# ESP32_CONTROLLER_SHEET.net
KiCad netlist of a schematic drawn in Altium Designer
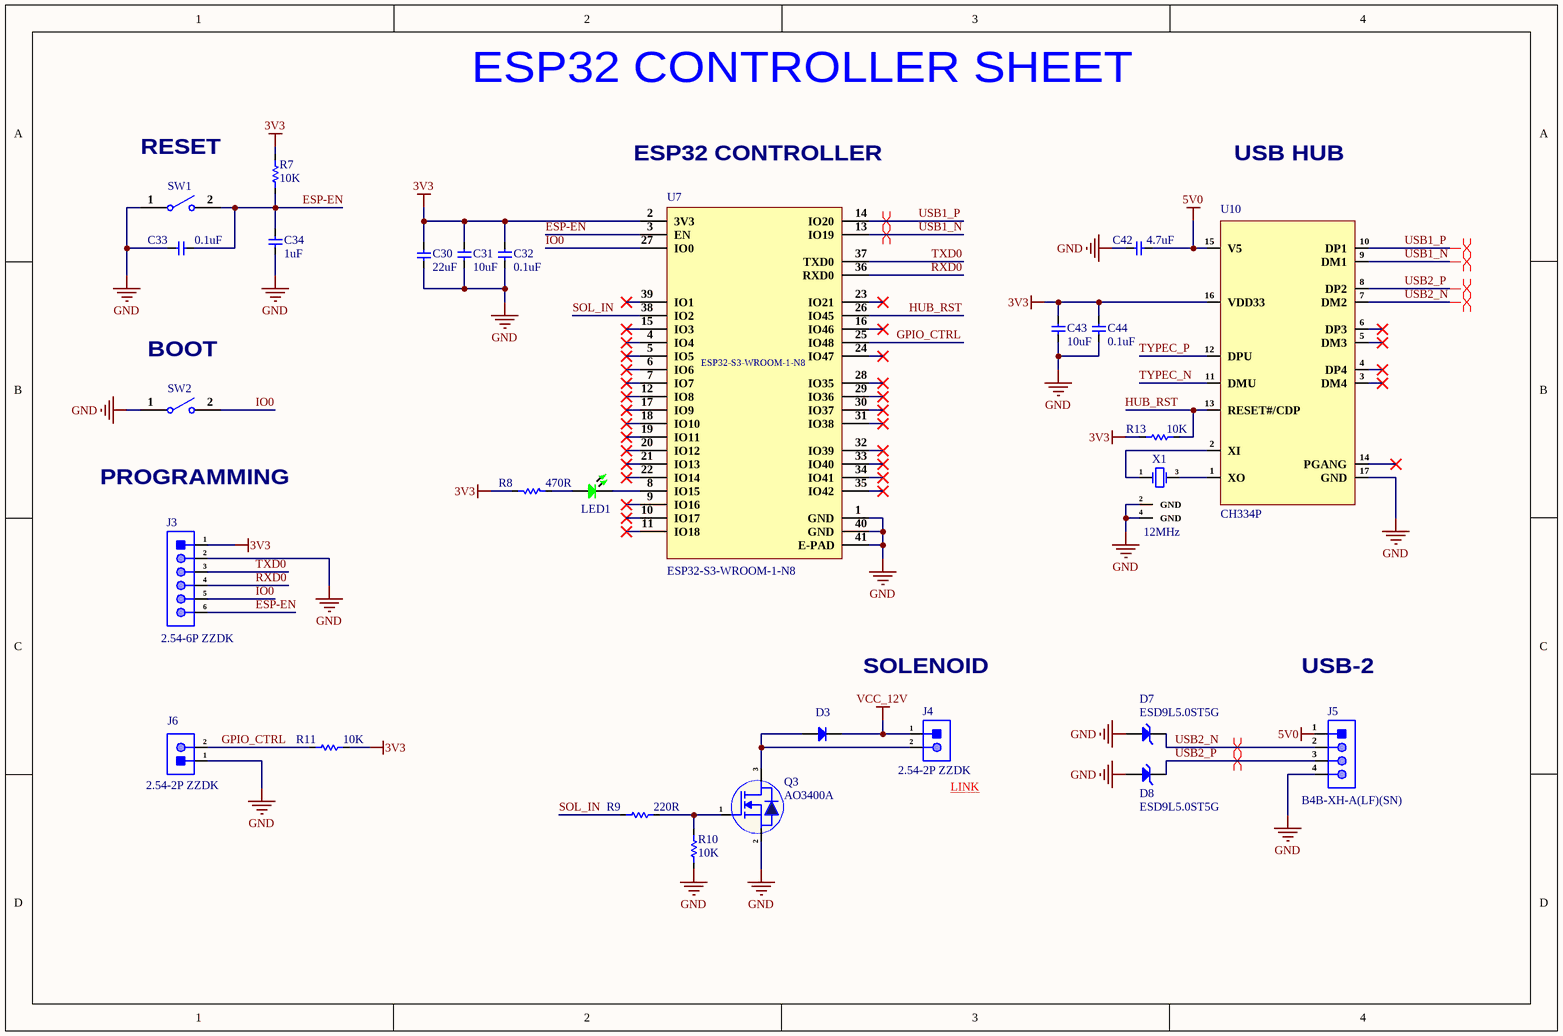
[diagram p0: ESP32_CONTROLLER_SHEET.SchDoc]

(export (version "E")
  (design (tool "Eeschema 10.0.6"))
  (components
    (comp (ref "C30")
      (value "22uF")
      (footprint "Cap-0603")
      (description "CAP CER 22UF 10V X5R 0603")
      (fields
        (field (name "MANUFACTURER") "Yageo")
        (field (name "MANUFACTURER PART NUMBER") "CC0603MRX5R6BB226")
      )
      (libsource (lib "eSpark Libraries") (part "CC0603MRX5R6BB226"))
    )
    (comp (ref "C31")
      (value "10uF")
      (footprint "Cap-0603")
      (description "CAP CER 10UF 16V X5R 0603")
      (fields
        (field (name "MANUFACTURER") "Yageo")
        (field (name "MANUFACTURER PART NUMBER") "CC0603KRX5R7BB106")
      )
      (libsource (lib "eSpark Libraries") (part "CC0603KRX5R7BB106"))
    )
    (comp (ref "C32")
      (value "0.1uF")
      (footprint "Cap-0402")
      (description "CAP CER 0.1UF 50V X7R 0402")
      (fields
        (field (name "MANUFACTURER") "Samsung")
        (field (name "MANUFACTURER PART NUMBER") "CL05B104KB54PNC")
      )
      (libsource (lib "eSpark Libraries") (part "CL05B104KB54PNC"))
    )
    (comp (ref "C33")
      (value "0.1uF")
      (footprint "Cap-0402")
      (description "CAP CER 0.1UF 50V X7R 0402")
      (fields
        (field (name "MANUFACTURER") "Samsung")
        (field (name "MANUFACTURER PART NUMBER") "CL05B104KB54PNC")
      )
      (libsource (lib "eSpark Libraries") (part "CL05B104KB54PNC"))
    )
    (comp (ref "C34")
      (value "1uF")
      (footprint "Cap-0402")
      (description "CAP CER 1UF 16V X5R 0402")
      (fields
        (field (name "MANUFACTURER") "Yageo")
        (field (name "MANUFACTURER PART NUMBER") "CC0402KRX5R7BB105")
      )
      (libsource (lib "eSpark Libraries") (part "CC0402KRX5R7BB105"))
    )
    (comp (ref "C42")
      (value "4.7uF")
      (footprint "Cap-0402")
      (description "CAP CER 4.7UF 16V X5R 0402")
      (fields
        (field (name "MANUFACTURER") "Samsung")
        (field (name "MANUFACTURER PART NUMBER") "CL05A475MO5NUNC")
      )
      (libsource (lib "eSpark Libraries") (part "CL05A475MO5NUNC"))
    )
    (comp (ref "C43")
      (value "10uF")
      (footprint "Cap-0603")
      (description "CAP CER 10UF 16V X5R 0603")
      (fields
        (field (name "MANUFACTURER") "Yageo")
        (field (name "MANUFACTURER PART NUMBER") "CC0603KRX5R7BB106")
      )
      (libsource (lib "eSpark Libraries") (part "CC0603KRX5R7BB106"))
    )
    (comp (ref "C44")
      (value "0.1uF")
      (footprint "Cap-0402")
      (description "CAP CER 0.1UF 50V X7R 0402")
      (fields
        (field (name "MANUFACTURER") "Samsung")
        (field (name "MANUFACTURER PART NUMBER") "CL05B104KB54PNC")
      )
      (libsource (lib "eSpark Libraries") (part "CL05B104KB54PNC"))
    )
    (comp (ref "D3")
      (value "1N4148W")
      (footprint "SOD-123")
      (description "100V 400mW Single 1.25V@150mA 8ns 300mA SOD-123 Switching Diode ROHS")
      (fields (field (name "MANUFACTURER") "JSMSEMI") (field (name "LCSC PART NUMBER") "C917030"))
      (libsource (lib "eSpark Libraries") (part "1N4148W"))
    )
    (comp (ref "D7")
      (value "ESD9L5.0ST5G")
      (footprint "SOD-923.")
      (fields (field (name "MANUFACTURER") "ON Semiconductor") (field (name "LCSC PART NUMBER") "C82326"))
      (libsource (lib "eSpark Libraries") (part "ESD9L5.0ST5G"))
    )
    (comp (ref "D8")
      (value "ESD9L5.0ST5G")
      (footprint "SOD-923.")
      (description "TVS DIODE 5V 9.8V SOD923")
      (fields (field (name "MANUFACTURER") "ON Semiconductor") (field (name "LCSC PART NUMBER") "C82326"))
      (libsource (lib "eSpark Libraries") (part "ESD9L5.0ST5G"))
    )
    (comp (ref "J3")
      (value "2.54-6P ZZDK")
      (footprint "2.54-6P ZZDK")
      (description "CONN HEADER TH 6POS 2.5mm")
      (fields (field (name "MANUFACTURER") "SHOU HAN") (field (name "LCSC PART NUMBER") "C18185653"))
      (libsource (lib "DOCK_ESP32_v1.0") (part "2.54-6P ZZDK"))
    )
    (comp (ref "J4")
      (value "2.54-2P ZZDK")
      (footprint "2.54-2P ZZDK")
      (fields (field (name "MANUFACTURER") "SHOU HAN") (field (name "LCSC PART NUMBER") "C18185649"))
      (libsource (lib "") (part "2.54-2P ZZDK_1"))
    )
    (comp (ref "J5")
      (value "B4B-XH-A(LF)(SN)")
      (footprint "B4B-XH-A(LF)(SN).")
      (description "CONN HEADER VERT 4POS 2.5MM")
      (fields (field (name "MANUFACTURER") "JST") (field (name "LCSC PART NUMBER") "C144395"))
      (libsource (lib "eSpark Libraries") (part "B4B-XH-A(LF)(SN)"))
    )
    (comp (ref "J6")
      (value "2.54-2P ZZDK")
      (footprint "2.54-2P ZZDK")
      (fields (field (name "MANUFACTURER") "SHOU HAN") (field (name "LCSC PART NUMBER") "C18185649"))
      (libsource (lib "eSpark Libraries") (part "2.54-2P ZZDK"))
    )
    (comp (ref "LED1")
      (value "Emerald")
      (footprint "LED-0603")
      (description "Emerald 0603 Light Emitting Diodes (LED) ROHS")
      (fields
        (field (name "MANUFACTURER") "Foshan NationStar Optoelectronics")
        (field (name "MANUFACTURER PART NUMBER") "NCD0603G2")
      )
      (libsource (lib "eSpark Libraries") (part "NCD0603G2"))
    )
    (comp (ref "Q3")
      (value "AO3400A")
      (footprint "sot-23")
      (description "30V 5.8A 32mΩ@10V,5.8A 1.4W 1.4V@250uA N Channel SOT-23 MOSFETs ROHS")
      (fields (field (name "MANUFACTURER") "BORN") (field (name "LCSC PART NUMBER") "C344010"))
      (libsource (lib "eSpark Libraries") (part "AO3400A"))
    )
    (comp (ref "R7")
      (value "10K")
      (footprint "Res-0402")
      (description "RES 10K OHM 1% 1/16W 0402")
      (fields
        (field (name "MANUFACTURER") "Yageo")
        (field (name "MANUFACTURER PART NUMBER") "RC0402FR-0710KL")
      )
      (libsource (lib "eSpark Libraries") (part "RC0402FR-0710KL"))
    )
    (comp (ref "R8")
      (value "470R")
      (footprint "Res-0402")
      (description "RES 470 OHM 1% 1/16W 0402")
      (fields
        (field (name "MANUFACTURER") "Yageo")
        (field (name "MANUFACTURER PART NUMBER") "RC0402FR-07470RL")
      )
      (libsource (lib "eSpark Libraries") (part "RC0402FR-07470RL"))
    )
    (comp (ref "R9")
      (value "220R")
      (footprint "Res-0402")
      (description "RES 220 OHM 1% 1/16W 0402")
      (fields (field (name "LCSC PART NUMBER") "C112291") (field (name "MANUFACTURER") "Yageo"))
      (libsource (lib "eSpark Libraries") (part "RC0402FR-07220RL"))
    )
    (comp (ref "R10")
      (value "10K")
      (footprint "Res-0402")
      (description "RES 10K OHM 1% 1/16W 0402")
      (fields
        (field (name "MANUFACTURER") "Yageo")
        (field (name "MANUFACTURER PART NUMBER") "RC0402FR-0710KL")
      )
      (libsource (lib "eSpark Libraries") (part "RC0402FR-0710KL"))
    )
    (comp (ref "R11")
      (value "10K")
      (footprint "Res-0402")
      (description "RES 10K OHM 1% 1/16W 0402")
      (fields
        (field (name "MANUFACTURER") "Yageo")
        (field (name "MANUFACTURER PART NUMBER") "RC0402FR-0710KL")
      )
      (libsource (lib "eSpark Libraries") (part "RC0402FR-0710KL"))
    )
    (comp (ref "R13")
      (value "10K")
      (footprint "Res-0402")
      (description "RES 10K OHM 1% 1/16W 0402")
      (fields
        (field (name "MANUFACTURER") "Yageo")
        (field (name "MANUFACTURER PART NUMBER") "RC0402FR-0710KL")
      )
      (libsource (lib "eSpark Libraries") (part "RC0402FR-0710KL"))
    )
    (comp (ref "SW1")
      (value "GT-TC032A-H015-L1")
      (footprint "GT-TC032A-H015-L1")
      (fields (field (name "MANUFACTURER") "G-Switch") (field (name "LCSC PART NUMBER") "C843684"))
      (libsource (lib "eSpark Libraries") (part "GT-TC032A-H015-L1"))
    )
    (comp (ref "SW2")
      (value "GT-TC032A-H015-L1")
      (footprint "GT-TC032A-H015-L1")
      (fields (field (name "MANUFACTURER") "G-Switch") (field (name "LCSC PART NUMBER") "C843684"))
      (libsource (lib "eSpark Libraries") (part "GT-TC032A-H015-L1"))
    )
    (comp (ref "U7")
      (value "ESP32-S3-WROOM-1-N8")
      (footprint "41-SMD Module")
      (description "ESP32-S3 chip 2.4GHz SMD,18x25.5mm WiFi Modules ROHS")
      (fields (field (name "MANUFACTURER") "Expressif System") (field (name "LCSC PART NUMBER") "C2913198"))
      (libsource (lib "eSpark Libraries") (part "ESP32-S3-WROOM-1-N8"))
    )
    (comp (ref "U10")
      (value "CH334P")
      (footprint "QFN-16")
      (description "480Mbps Hub USB 2.0 QFN-16(3x3) Interface Controllers RoHS")
      (fields (field (name "LCSC PART NUMBER") "C5373042"))
      (libsource (lib "DOCK_ESP32_v1.0") (part "CH334P"))
    )
    (comp (ref "X1")
      (value "12MHz")
      (footprint "SMD2520-4P")
      (description "12MHz 18pF ±10ppm SMD2520-4P Crystals ROHS")
      (fields (field (name "MANUFACTURER") "JYJE") (field (name "MANUFACTURER PART NUMBER") "2TJ412000XYGBC"))
      (libsource (lib "eSpark Libraries") (part "2TJ412000XYGBC"))
    )
  )
  (nets
    (net (code "1") (name "/ESP-EN") (class "Default")
      (node (ref "C33") (pin "1") (pinfunction "1_1") (pintype "passive"))
      (node (ref "C34") (pin "2") (pinfunction "2_2") (pintype "passive"))
      (node (ref "J3") (pin "6") (pinfunction "6_6") (pintype "passive"))
      (node (ref "R7") (pin "1") (pinfunction "1_1") (pintype "passive"))
      (node (ref "SW1") (pin "2") (pinfunction "2_2") (pintype "passive"))
      (node (ref "U7") (pin "3") (pinfunction "EN_3") (pintype "passive"))
    )
    (net (code "2") (name "/GPIO_CTRL") (class "Default")
      (node (ref "J6") (pin "2") (pinfunction "2_2") (pintype "passive"))
      (node (ref "R11") (pin "1") (pinfunction "1_1") (pintype "passive"))
      (node (ref "U7") (pin "25") (pinfunction "IO48_25") (pintype "passive"))
    )
    (net (code "3") (name "/HUB_RST") (class "Default")
      (node (ref "R13") (pin "1") (pinfunction "1_1") (pintype "passive"))
      (node (ref "U10") (pin "13") (pinfunction "RESET#/CDP_13") (pintype "passive"))
      (node (ref "U7") (pin "26") (pinfunction "IO45_26") (pintype "passive"))
    )
    (net (code "4") (name "/IO0") (class "Default")
      (node (ref "J3") (pin "5") (pinfunction "5_5") (pintype "passive"))
      (node (ref "SW2") (pin "2") (pinfunction "2_2") (pintype "passive"))
      (node (ref "U7") (pin "27") (pinfunction "IO0_27") (pintype "passive"))
    )
    (net (code "5") (name "/RXD0") (class "Default")
      (node (ref "J3") (pin "4") (pinfunction "4_4") (pintype "passive"))
      (node (ref "U7") (pin "36") (pinfunction "RXD0_36") (pintype "passive"))
    )
    (net (code "6") (name "/SOL_IN") (class "Default")
      (node (ref "R9") (pin "1") (pinfunction "1_1") (pintype "passive"))
      (node (ref "U7") (pin "38") (pinfunction "IO2_38") (pintype "passive"))
    )
    (net (code "7") (name "/TXD0") (class "Default")
      (node (ref "J3") (pin "3") (pinfunction "3_3") (pintype "passive"))
      (node (ref "U7") (pin "37") (pinfunction "TXD0_37") (pintype "passive"))
    )
    (net (code "8") (name "/TYPEC_N") (class "Default")
      (node (ref "U10") (pin "11") (pinfunction "DMU_11") (pintype "passive"))
    )
    (net (code "9") (name "/TYPEC_P") (class "Default")
      (node (ref "U10") (pin "12") (pinfunction "DPU_12") (pintype "passive"))
    )
    (net (code "10") (name "/USB1_N") (class "Default")
      (node (ref "U10") (pin "9") (pinfunction "DM1_9") (pintype "passive"))
      (node (ref "U7") (pin "13") (pinfunction "IO19_13") (pintype "passive"))
    )
    (net (code "11") (name "/USB1_P") (class "Default")
      (node (ref "U10") (pin "10") (pinfunction "DP1_10") (pintype "passive"))
      (node (ref "U7") (pin "14") (pinfunction "IO20_14") (pintype "passive"))
    )
    (net (code "12") (name "/USB2_N") (class "Default")
      (node (ref "D7") (pin "1") (pinfunction "K_1") (pintype "passive"))
      (node (ref "J5") (pin "2") (pinfunction "2_2") (pintype "passive"))
      (node (ref "U10") (pin "7") (pinfunction "DM2_7") (pintype "passive"))
    )
    (net (code "13") (name "/USB2_P") (class "Default")
      (node (ref "D8") (pin "1") (pinfunction "K_1") (pintype "passive"))
      (node (ref "J5") (pin "3") (pinfunction "3_3") (pintype "passive"))
      (node (ref "U10") (pin "8") (pinfunction "DP2_8") (pintype "passive"))
    )
    (net (code "14") (name "3V3") (class "Default")
      (node (ref "C30") (pin "2") (pinfunction "2_2") (pintype "passive"))
      (node (ref "C31") (pin "1") (pinfunction "1_1") (pintype "passive"))
      (node (ref "C32") (pin "1") (pinfunction "1_1") (pintype "passive"))
      (node (ref "C43") (pin "1") (pinfunction "1_1") (pintype "passive"))
      (node (ref "C44") (pin "1") (pinfunction "1_1") (pintype "passive"))
      (node (ref "J3") (pin "1") (pinfunction "1_1") (pintype "passive"))
      (node (ref "R11") (pin "2") (pinfunction "2_2") (pintype "passive"))
      (node (ref "R13") (pin "2") (pinfunction "2_2") (pintype "passive"))
      (node (ref "R7") (pin "2") (pinfunction "2_2") (pintype "passive"))
      (node (ref "R8") (pin "2") (pinfunction "2_2") (pintype "passive"))
      (node (ref "U10") (pin "16") (pinfunction "VDD33_16") (pintype "passive"))
      (node (ref "U7") (pin "2") (pinfunction "3V3_2") (pintype "passive"))
    )
    (net (code "15") (name "5V0") (class "Default")
      (node (ref "C42") (pin "2") (pinfunction "2_2") (pintype "passive"))
      (node (ref "J5") (pin "1") (pinfunction "1_1") (pintype "passive"))
      (node (ref "U10") (pin "15") (pinfunction "V5_15") (pintype "passive"))
    )
    (net (code "16") (name "GND") (class "Default")
      (node (ref "C30") (pin "1") (pinfunction "1_1") (pintype "passive"))
      (node (ref "C31") (pin "2") (pinfunction "2_2") (pintype "passive"))
      (node (ref "C32") (pin "2") (pinfunction "2_2") (pintype "passive"))
      (node (ref "C33") (pin "2") (pinfunction "2_2") (pintype "passive"))
      (node (ref "C34") (pin "1") (pinfunction "1_1") (pintype "passive"))
      (node (ref "C42") (pin "1") (pinfunction "1_1") (pintype "passive"))
      (node (ref "C43") (pin "2") (pinfunction "2_2") (pintype "passive"))
      (node (ref "C44") (pin "2") (pinfunction "2_2") (pintype "passive"))
      (node (ref "D7") (pin "2") (pinfunction "A_2") (pintype "passive"))
      (node (ref "D8") (pin "2") (pinfunction "A_2") (pintype "passive"))
      (node (ref "J3") (pin "2") (pinfunction "2_2") (pintype "passive"))
      (node (ref "J5") (pin "4") (pinfunction "4_4") (pintype "passive"))
      (node (ref "J6") (pin "1") (pinfunction "1_1") (pintype "passive"))
      (node (ref "Q3") (pin "2") (pinfunction "S_2") (pintype "passive"))
      (node (ref "R10") (pin "1") (pinfunction "1_1") (pintype "passive"))
      (node (ref "SW1") (pin "1") (pinfunction "1_1") (pintype "passive"))
      (node (ref "SW2") (pin "1") (pinfunction "1_1") (pintype "passive"))
      (node (ref "U10") (pin "17") (pinfunction "GND_17") (pintype "passive"))
      (node (ref "U7") (pin "1") (pinfunction "GND_1") (pintype "passive"))
      (node (ref "U7") (pin "40") (pinfunction "GND_40") (pintype "passive"))
      (node (ref "U7") (pin "41") (pinfunction "E-PAD_41") (pintype "passive"))
      (node (ref "X1") (pin "2") (pinfunction "GND_2") (pintype "passive"))
      (node (ref "X1") (pin "4") (pinfunction "GND_4") (pintype "passive"))
    )
    (net (code "17") (name "Net-(D3-A)") (class "Default")
      (node (ref "D3") (pin "1") (pinfunction "A_1") (pintype "passive"))
      (node (ref "J4") (pin "2") (pinfunction "2_2") (pintype "passive"))
      (node (ref "Q3") (pin "3") (pinfunction "D_3") (pintype "passive"))
    )
    (net (code "18") (name "Net-(LED1-Pad1)") (class "Default")
      (node (ref "LED1") (pin "1") (pinfunction "1_1") (pintype "passive"))
      (node (ref "R8") (pin "1") (pinfunction "1_1") (pintype "passive"))
    )
    (net (code "19") (name "Net-(Q3-G)") (class "Default")
      (node (ref "Q3") (pin "1") (pinfunction "G_1") (pintype "passive"))
      (node (ref "R10") (pin "2") (pinfunction "2_2") (pintype "passive"))
      (node (ref "R9") (pin "2") (pinfunction "2_2") (pintype "passive"))
    )
    (net (code "20") (name "Net-(U7-IO15)") (class "Default")
      (node (ref "LED1") (pin "2") (pinfunction "2_2") (pintype "passive"))
      (node (ref "U7") (pin "8") (pinfunction "IO15_8") (pintype "passive"))
    )
    (net (code "21") (name "Net-(U10-XI)") (class "Default")
      (node (ref "U10") (pin "2") (pinfunction "XI_2") (pintype "passive"))
      (node (ref "X1") (pin "1") (pinfunction "OSC1_1") (pintype "passive"))
    )
    (net (code "22") (name "Net-(U10-XO)") (class "Default")
      (node (ref "U10") (pin "1") (pinfunction "XO_1") (pintype "passive"))
      (node (ref "X1") (pin "3") (pinfunction "OSC2_3") (pintype "passive"))
    )
    (net (code "23") (name "VCC_12V") (class "Default")
      (node (ref "D3") (pin "2") (pinfunction "K_2") (pintype "passive"))
      (node (ref "J4") (pin "1") (pinfunction "1_1") (pintype "passive"))
    )
    (net (code "24") (name "unconnected-(U7-IO1-Pad39)") (class "Default")
      (node (ref "U7") (pin "39") (pinfunction "IO1_39") (pintype "passive+no_connect"))
    )
    (net (code "25") (name "unconnected-(U7-IO3-Pad15)") (class "Default")
      (node (ref "U7") (pin "15") (pinfunction "IO3_15") (pintype "passive+no_connect"))
    )
    (net (code "26") (name "unconnected-(U7-IO4-Pad4)") (class "Default")
      (node (ref "U7") (pin "4") (pinfunction "IO4_4") (pintype "passive+no_connect"))
    )
    (net (code "27") (name "unconnected-(U7-IO5-Pad5)") (class "Default")
      (node (ref "U7") (pin "5") (pinfunction "IO5_5") (pintype "passive+no_connect"))
    )
    (net (code "28") (name "unconnected-(U7-IO6-Pad6)") (class "Default")
      (node (ref "U7") (pin "6") (pinfunction "IO6_6") (pintype "passive+no_connect"))
    )
    (net (code "29") (name "unconnected-(U7-IO7-Pad7)") (class "Default")
      (node (ref "U7") (pin "7") (pinfunction "IO7_7") (pintype "passive+no_connect"))
    )
    (net (code "30") (name "unconnected-(U7-IO8-Pad12)") (class "Default")
      (node (ref "U7") (pin "12") (pinfunction "IO8_12") (pintype "passive+no_connect"))
    )
    (net (code "31") (name "unconnected-(U7-IO9-Pad17)") (class "Default")
      (node (ref "U7") (pin "17") (pinfunction "IO9_17") (pintype "passive+no_connect"))
    )
    (net (code "32") (name "unconnected-(U7-IO10-Pad18)") (class "Default")
      (node (ref "U7") (pin "18") (pinfunction "IO10_18") (pintype "passive+no_connect"))
    )
    (net (code "33") (name "unconnected-(U7-IO11-Pad19)") (class "Default")
      (node (ref "U7") (pin "19") (pinfunction "IO11_19") (pintype "passive+no_connect"))
    )
    (net (code "34") (name "unconnected-(U7-IO12-Pad20)") (class "Default")
      (node (ref "U7") (pin "20") (pinfunction "IO12_20") (pintype "passive+no_connect"))
    )
    (net (code "35") (name "unconnected-(U7-IO13-Pad21)") (class "Default")
      (node (ref "U7") (pin "21") (pinfunction "IO13_21") (pintype "passive+no_connect"))
    )
    (net (code "36") (name "unconnected-(U7-IO14-Pad22)") (class "Default")
      (node (ref "U7") (pin "22") (pinfunction "IO14_22") (pintype "passive+no_connect"))
    )
    (net (code "37") (name "unconnected-(U7-IO16-Pad9)") (class "Default")
      (node (ref "U7") (pin "9") (pinfunction "IO16_9") (pintype "passive+no_connect"))
    )
    (net (code "38") (name "unconnected-(U7-IO17-Pad10)") (class "Default")
      (node (ref "U7") (pin "10") (pinfunction "IO17_10") (pintype "passive+no_connect"))
    )
    (net (code "39") (name "unconnected-(U7-IO18-Pad11)") (class "Default")
      (node (ref "U7") (pin "11") (pinfunction "IO18_11") (pintype "passive+no_connect"))
    )
    (net (code "40") (name "unconnected-(U7-IO21-Pad23)") (class "Default")
      (node (ref "U7") (pin "23") (pinfunction "IO21_23") (pintype "passive+no_connect"))
    )
    (net (code "41") (name "unconnected-(U7-IO35-Pad28)") (class "Default")
      (node (ref "U7") (pin "28") (pinfunction "IO35_28") (pintype "passive+no_connect"))
    )
    (net (code "42") (name "unconnected-(U7-IO36-Pad29)") (class "Default")
      (node (ref "U7") (pin "29") (pinfunction "IO36_29") (pintype "passive+no_connect"))
    )
    (net (code "43") (name "unconnected-(U7-IO37-Pad30)") (class "Default")
      (node (ref "U7") (pin "30") (pinfunction "IO37_30") (pintype "passive+no_connect"))
    )
    (net (code "44") (name "unconnected-(U7-IO38-Pad31)") (class "Default")
      (node (ref "U7") (pin "31") (pinfunction "IO38_31") (pintype "passive+no_connect"))
    )
    (net (code "45") (name "unconnected-(U7-IO39-Pad32)") (class "Default")
      (node (ref "U7") (pin "32") (pinfunction "IO39_32") (pintype "passive+no_connect"))
    )
    (net (code "46") (name "unconnected-(U7-IO40-Pad33)") (class "Default")
      (node (ref "U7") (pin "33") (pinfunction "IO40_33") (pintype "passive+no_connect"))
    )
    (net (code "47") (name "unconnected-(U7-IO41-Pad34)") (class "Default")
      (node (ref "U7") (pin "34") (pinfunction "IO41_34") (pintype "passive+no_connect"))
    )
    (net (code "48") (name "unconnected-(U7-IO42-Pad35)") (class "Default")
      (node (ref "U7") (pin "35") (pinfunction "IO42_35") (pintype "passive+no_connect"))
    )
    (net (code "49") (name "unconnected-(U7-IO46-Pad16)") (class "Default")
      (node (ref "U7") (pin "16") (pinfunction "IO46_16") (pintype "passive+no_connect"))
    )
    (net (code "50") (name "unconnected-(U7-IO47-Pad24)") (class "Default")
      (node (ref "U7") (pin "24") (pinfunction "IO47_24") (pintype "passive+no_connect"))
    )
    (net (code "51") (name "unconnected-(U10-DM3-Pad5)") (class "Default")
      (node (ref "U10") (pin "5") (pinfunction "DM3_5") (pintype "passive+no_connect"))
    )
    (net (code "52") (name "unconnected-(U10-DM4-Pad3)") (class "Default")
      (node (ref "U10") (pin "3") (pinfunction "DM4_3") (pintype "passive+no_connect"))
    )
    (net (code "53") (name "unconnected-(U10-DP3-Pad6)") (class "Default")
      (node (ref "U10") (pin "6") (pinfunction "DP3_6") (pintype "passive+no_connect"))
    )
    (net (code "54") (name "unconnected-(U10-DP4-Pad4)") (class "Default")
      (node (ref "U10") (pin "4") (pinfunction "DP4_4") (pintype "passive+no_connect"))
    )
    (net (code "55") (name "unconnected-(U10-PGANG-Pad14)") (class "Default")
      (node (ref "U10") (pin "14") (pinfunction "PGANG_14") (pintype "passive+no_connect"))
    )
  )
)
